# TMC6200_BOB.net
KiCad netlist of a schematic drawn in Altium Designer
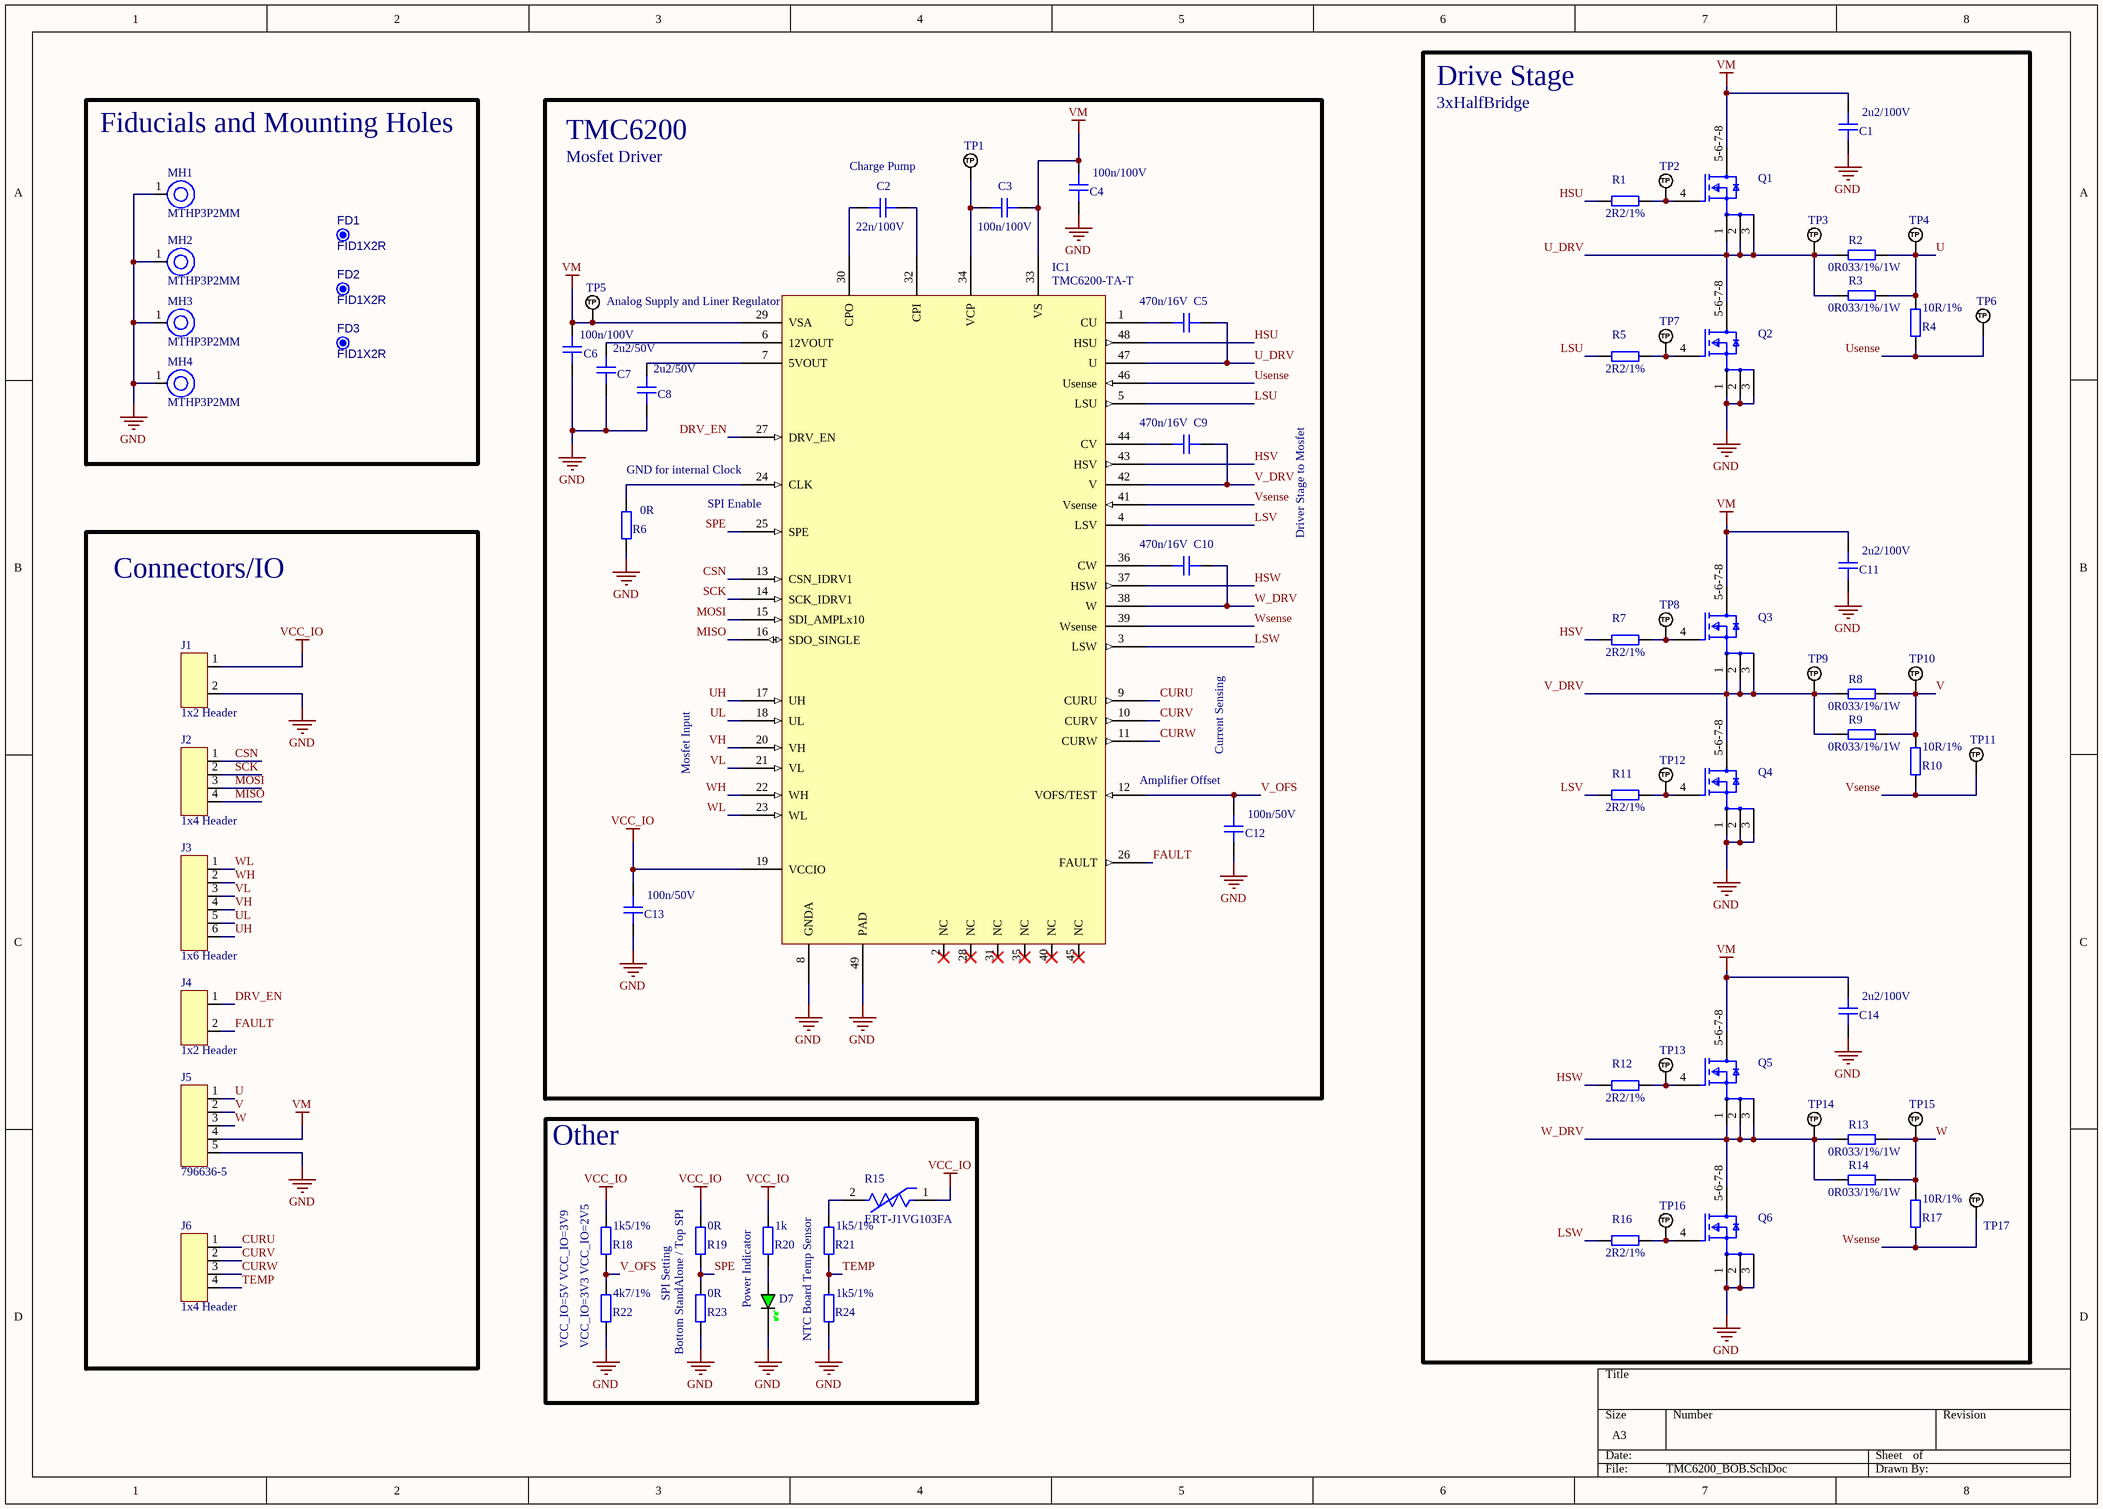
[diagram p0: TMC6200_BOB.SchDoc]

(export (version "E")
  (design (tool "Eeschema 10.0.6"))
  (components
    (comp (ref "C1")
      (value "2u2/100V")
      (footprint "CAP_1206")
      (description "Capacitor SMD 1206")
      (fields (field (name "SOURCE") "Schematic-Lib-PhilsLab.SchLib"))
      (libsource (lib "Leonhard Waibl") (part "CAP_EL_NP_5MM"))
    )
    (comp (ref "C2")
      (value "22n/100V")
      (footprint "CAP_0603")
      (description "Capacitor SMD 0603")
      (fields (field (name "SOURCE") "Schematic-Lib-PhilsLab.SchLib"))
      (libsource (lib "Leonhard Waibl") (part "CAP_EL_NP_5MM"))
    )
    (comp (ref "C3")
      (value "100n/100V")
      (footprint "CAP_0805")
      (description "Capacitor SMD 0805")
      (fields (field (name "SOURCE") "Schematic-Lib-PhilsLab.SchLib"))
      (libsource (lib "Leonhard Waibl") (part "CAP_EL_NP_5MM"))
    )
    (comp (ref "C4")
      (value "100n/100V")
      (footprint "CAP_0805")
      (description "Capacitor SMD 0805")
      (fields (field (name "SOURCE") "Schematic-Lib-PhilsLab.SchLib"))
      (libsource (lib "Leonhard Waibl") (part "CAP_EL_NP_5MM"))
    )
    (comp (ref "C5")
      (value "470n/16V")
      (footprint "CAP_0603")
      (description "Capacitor SMD 0603")
      (fields (field (name "SOURCE") "Schematic-Lib-PhilsLab.SchLib"))
      (libsource (lib "Leonhard Waibl") (part "CAP_EL_NP_5MM"))
    )
    (comp (ref "C6")
      (value "100n/100V")
      (footprint "CAP_0805")
      (description "Capacitor SMD 0805")
      (fields (field (name "SOURCE") "Schematic-Lib-PhilsLab.SchLib"))
      (libsource (lib "Leonhard Waibl") (part "CAP_EL_NP_5MM"))
    )
    (comp (ref "C7")
      (value "2u2/50V")
      (footprint "CAP_0805")
      (description "Capacitor SMD 0805")
      (fields (field (name "SOURCE") "Schematic-Lib-PhilsLab.SchLib"))
      (libsource (lib "Leonhard Waibl") (part "CAP_EL_NP_5MM"))
    )
    (comp (ref "C8")
      (value "2u2/50V")
      (footprint "CAP_0805")
      (description "Capacitor SMD 0805")
      (fields (field (name "SOURCE") "Schematic-Lib-PhilsLab.SchLib"))
      (libsource (lib "Leonhard Waibl") (part "CAP_EL_NP_5MM"))
    )
    (comp (ref "C9")
      (value "470n/16V")
      (footprint "CAP_0603")
      (description "Capacitor SMD 0603")
      (fields (field (name "SOURCE") "Schematic-Lib-PhilsLab.SchLib"))
      (libsource (lib "Leonhard Waibl") (part "CAP_EL_NP_5MM"))
    )
    (comp (ref "C10")
      (value "470n/16V")
      (footprint "CAP_0603")
      (description "Capacitor SMD 0603")
      (fields (field (name "SOURCE") "Schematic-Lib-PhilsLab.SchLib"))
      (libsource (lib "Leonhard Waibl") (part "CAP_EL_NP_5MM"))
    )
    (comp (ref "C11")
      (value "2u2/100V")
      (footprint "CAP_1206")
      (description "Capacitor SMD 1206")
      (fields (field (name "SOURCE") "Schematic-Lib-PhilsLab.SchLib"))
      (libsource (lib "Leonhard Waibl") (part "CAP_EL_NP_5MM"))
    )
    (comp (ref "C12")
      (value "100n/50V")
      (footprint "CAP_0603")
      (description "Capacitor SMD 0603")
      (fields (field (name "SOURCE") "Schematic-Lib-PhilsLab.SchLib"))
      (libsource (lib "Leonhard Waibl") (part "CAP_EL_NP_5MM"))
    )
    (comp (ref "C13")
      (value "100n/50V")
      (footprint "CAP_0603")
      (description "Capacitor SMD 0603")
      (fields (field (name "SOURCE") "Schematic-Lib-PhilsLab.SchLib"))
      (libsource (lib "Leonhard Waibl") (part "CAP_EL_NP_5MM"))
    )
    (comp (ref "C14")
      (value "2u2/100V")
      (footprint "CAP_1206")
      (description "Capacitor SMD 1206")
      (fields (field (name "SOURCE") "Schematic-Lib-PhilsLab.SchLib"))
      (libsource (lib "Leonhard Waibl") (part "CAP_EL_NP_5MM"))
    )
    (comp (ref "D7")
      (value "LED_0805_GREEN")
      (footprint "LED_0805_GREEN")
      (description "LED 0805 GREEN SMD")
      (fields (field (name "SOURCE") "Schematic-Lib-PhilsLab.SchLib"))
      (libsource (lib "Leonhard Waibl") (part "LED_0805_GREEN"))
    )
    (comp (ref "FD1")
      (value "FID1X2R")
      (footprint "FID1X2R")
      (description "Fiducial - Round 1x2mm")
      (libsource (lib "Leonhard Waibl") (part "CMP-00134-2"))
    )
    (comp (ref "FD2")
      (value "FID1X2R")
      (footprint "FID1X2R")
      (description "Fiducial - Round 1x2mm")
      (libsource (lib "Leonhard Waibl") (part "CMP-00134-2"))
    )
    (comp (ref "FD3")
      (value "FID1X2R")
      (footprint "FID1X2R")
      (description "Fiducial - Round 1x2mm")
      (libsource (lib "Leonhard Waibl") (part "CMP-00134-2"))
    )
    (comp (ref "IC1")
      (value "TMC6200-TA-T")
      (footprint "TSQFP50P900X900X120_HS-49N")
      (libsource (lib "Leonhard Waibl") (part "TMC6200-TA-T-Symbol-1"))
    )
    (comp (ref "J1")
      (value "1x2 Header")
      (footprint "1x2 Header-Footprint-1")
      (libsource (lib "Leonhard Waibl") (part "1x2 Header-Symbol-1"))
    )
    (comp (ref "J2")
      (value "1x4 Header")
      (footprint "1x4 Header-Footprint-1")
      (libsource (lib "Leonhard Waibl") (part "1x4 Header-Symbol-1"))
    )
    (comp (ref "J3")
      (value "1x6 Header")
      (footprint "1x6 Header-Footprint-1")
      (libsource (lib "Leonhard Waibl") (part "1x6 Header-Symbol-1"))
    )
    (comp (ref "J4")
      (value "1x2 Header")
      (footprint "1x2 Header-Footprint-1")
      (libsource (lib "Leonhard Waibl") (part "1x2 Header-Symbol-1"))
    )
    (comp (ref "J5")
      (value "796636-5")
      (footprint "796636-5-Footprint-1")
      (libsource (lib "Leonhard Waibl") (part "796636-Symbol"))
    )
    (comp (ref "J6")
      (value "1x4 Header")
      (footprint "1x4 Header-Footprint-1")
      (libsource (lib "Leonhard Waibl") (part "1x4 Header-Symbol-1"))
    )
    (comp (ref "MH1")
      (value "MTHP3P2MM")
      (footprint "MTHP3P2MM-Footprint-1")
      (description "Mounting Hole Plated 3.2 mm drill")
      (libsource (lib "Leonhard Waibl") (part "MTHP3P2MM"))
    )
    (comp (ref "MH2")
      (value "MTHP3P2MM")
      (footprint "MTHP3P2MM-Footprint-1")
      (description "Mounting Hole Plated 3.2 mm drill")
      (libsource (lib "Leonhard Waibl") (part "MTHP3P2MM"))
    )
    (comp (ref "MH3")
      (value "MTHP3P2MM")
      (footprint "MTHP3P2MM-Footprint-1")
      (description "Mounting Hole Plated 3.2 mm drill")
      (libsource (lib "Leonhard Waibl") (part "MTHP3P2MM"))
    )
    (comp (ref "MH4")
      (value "MTHP3P2MM")
      (footprint "MTHP3P2MM-Footprint-1")
      (description "Mounting Hole Plated 3.2 mm drill")
      (libsource (lib "Leonhard Waibl") (part "MTHP3P2MM"))
    )
    (comp (ref "Q1")
      (value "SIDR626LDP-T1-RE3")
      (footprint "FP-T21-0014-SINGLE-MFG")
      (description "Mosfet, N-Ch, 60V, 204A, Powerpak So Rohs Compliant: Yes")
      (libsource (lib "Leonhard Waibl") (part "bca9987edd56f2da107db22e16ec776"))
    )
    (comp (ref "Q2")
      (value "SIDR626LDP-T1-RE3")
      (footprint "FP-T21-0014-SINGLE-MFG")
      (description "Mosfet, N-Ch, 60V, 204A, Powerpak So Rohs Compliant: Yes")
      (libsource (lib "Leonhard Waibl") (part "bca9987edd56f2da107db22e16ec776"))
    )
    (comp (ref "Q3")
      (value "SIDR626LDP-T1-RE3")
      (footprint "FP-T21-0014-SINGLE-MFG")
      (description "Mosfet, N-Ch, 60V, 204A, Powerpak So Rohs Compliant: Yes")
      (libsource (lib "Leonhard Waibl") (part "bca9987edd56f2da107db22e16ec776"))
    )
    (comp (ref "Q4")
      (value "SIDR626LDP-T1-RE3")
      (footprint "FP-T21-0014-SINGLE-MFG")
      (description "Mosfet, N-Ch, 60V, 204A, Powerpak So Rohs Compliant: Yes")
      (libsource (lib "Leonhard Waibl") (part "bca9987edd56f2da107db22e16ec776"))
    )
    (comp (ref "Q5")
      (value "SIDR626LDP-T1-RE3")
      (footprint "FP-T21-0014-SINGLE-MFG")
      (description "Mosfet, N-Ch, 60V, 204A, Powerpak So Rohs Compliant: Yes")
      (libsource (lib "Leonhard Waibl") (part "bca9987edd56f2da107db22e16ec776"))
    )
    (comp (ref "Q6")
      (value "SIDR626LDP-T1-RE3")
      (footprint "FP-T21-0014-SINGLE-MFG")
      (description "Mosfet, N-Ch, 60V, 204A, Powerpak So Rohs Compliant: Yes")
      (libsource (lib "Leonhard Waibl") (part "bca9987edd56f2da107db22e16ec776"))
    )
    (comp (ref "R1")
      (value "2R2/1%")
      (footprint "RES_0603")
      (description "Resistor SMD 0603")
      (fields (field (name "SOURCE") "Schematic-Lib-PhilsLab.SchLib"))
      (libsource (lib "Leonhard Waibl") (part "RES_5931"))
    )
    (comp (ref "R2")
      (value "0R033/1%/1W")
      (footprint "RES_1206")
      (description "Resistor SMD 1206")
      (fields (field (name "SOURCE") "Schematic-Lib-PhilsLab.SchLib"))
      (libsource (lib "Leonhard Waibl") (part "RES_5931"))
    )
    (comp (ref "R3")
      (value "0R033/1%/1W")
      (footprint "RES_1206")
      (description "Resistor SMD 1206")
      (fields (field (name "SOURCE") "Schematic-Lib-PhilsLab.SchLib"))
      (libsource (lib "Leonhard Waibl") (part "RES_5931"))
    )
    (comp (ref "R4")
      (value "10R/1%")
      (footprint "RES_0603")
      (description "Resistor SMD 0603")
      (fields (field (name "SOURCE") "Schematic-Lib-PhilsLab.SchLib"))
      (libsource (lib "Leonhard Waibl") (part "RES_5931"))
    )
    (comp (ref "R5")
      (value "2R2/1%")
      (footprint "RES_0603")
      (description "Resistor SMD 0603")
      (fields (field (name "SOURCE") "Schematic-Lib-PhilsLab.SchLib"))
      (libsource (lib "Leonhard Waibl") (part "RES_5931"))
    )
    (comp (ref "R6")
      (value "0R")
      (footprint "RES_0603")
      (description "Resistor SMD 0603")
      (fields (field (name "SOURCE") "Schematic-Lib-PhilsLab.SchLib"))
      (libsource (lib "Leonhard Waibl") (part "RES_5931"))
    )
    (comp (ref "R7")
      (value "2R2/1%")
      (footprint "RES_0603")
      (description "Resistor SMD 0603")
      (fields (field (name "SOURCE") "Schematic-Lib-PhilsLab.SchLib"))
      (libsource (lib "Leonhard Waibl") (part "RES_5931"))
    )
    (comp (ref "R8")
      (value "0R033/1%/1W")
      (footprint "RES_1206")
      (description "Resistor SMD 1206")
      (fields (field (name "SOURCE") "Schematic-Lib-PhilsLab.SchLib"))
      (libsource (lib "Leonhard Waibl") (part "RES_5931"))
    )
    (comp (ref "R9")
      (value "0R033/1%/1W")
      (footprint "RES_1206")
      (description "Resistor SMD 1206")
      (fields (field (name "SOURCE") "Schematic-Lib-PhilsLab.SchLib"))
      (libsource (lib "Leonhard Waibl") (part "RES_5931"))
    )
    (comp (ref "R10")
      (value "10R/1%")
      (footprint "RES_0603")
      (description "Resistor SMD 0603")
      (fields (field (name "SOURCE") "Schematic-Lib-PhilsLab.SchLib"))
      (libsource (lib "Leonhard Waibl") (part "RES_5931"))
    )
    (comp (ref "R11")
      (value "2R2/1%")
      (footprint "RES_0603")
      (description "Resistor SMD 0603")
      (fields (field (name "SOURCE") "Schematic-Lib-PhilsLab.SchLib"))
      (libsource (lib "Leonhard Waibl") (part "RES_5931"))
    )
    (comp (ref "R12")
      (value "2R2/1%")
      (footprint "RES_0603")
      (description "Resistor SMD 0603")
      (fields (field (name "SOURCE") "Schematic-Lib-PhilsLab.SchLib"))
      (libsource (lib "Leonhard Waibl") (part "RES_5931"))
    )
    (comp (ref "R13")
      (value "0R033/1%/1W")
      (footprint "RES_1206")
      (description "Resistor SMD 1206")
      (fields (field (name "SOURCE") "Schematic-Lib-PhilsLab.SchLib"))
      (libsource (lib "Leonhard Waibl") (part "RES_5931"))
    )
    (comp (ref "R14")
      (value "0R033/1%/1W")
      (footprint "RES_1206")
      (description "Resistor SMD 1206")
      (fields (field (name "SOURCE") "Schematic-Lib-PhilsLab.SchLib"))
      (libsource (lib "Leonhard Waibl") (part "RES_5931"))
    )
    (comp (ref "R15")
      (value "ERT-J1VG103FA")
      (footprint "FP-ERTJ1-MFG")
      (description "THERMISTOR NTC 10KOHM 3380K 0603")
      (fields (field (name "TOLERANCE") "1%"))
      (libsource (lib "Altium Content Vault") (part "3b148a6ebabc5fb4d708a66c052d352"))
    )
    (comp (ref "R16")
      (value "2R2/1%")
      (footprint "RES_0603")
      (description "Resistor SMD 0603")
      (fields (field (name "SOURCE") "Schematic-Lib-PhilsLab.SchLib"))
      (libsource (lib "Leonhard Waibl") (part "RES_5931"))
    )
    (comp (ref "R17")
      (value "10R/1%")
      (footprint "RES_0603")
      (description "Resistor SMD 0603")
      (fields (field (name "SOURCE") "Schematic-Lib-PhilsLab.SchLib"))
      (libsource (lib "Leonhard Waibl") (part "RES_5931"))
    )
    (comp (ref "R18")
      (value "1k5/1%")
      (footprint "RES_0603")
      (description "Resistor SMD 0603")
      (fields (field (name "SOURCE") "Schematic-Lib-PhilsLab.SchLib"))
      (libsource (lib "Leonhard Waibl") (part "RES_5931"))
    )
    (comp (ref "R19")
      (value "0R")
      (footprint "RES_0603")
      (description "Resistor SMD 0603")
      (fields (field (name "SOURCE") "Schematic-Lib-PhilsLab.SchLib"))
      (libsource (lib "Leonhard Waibl") (part "RES_5931"))
    )
    (comp (ref "R20")
      (value "1k")
      (footprint "RES_0603")
      (description "Resistor SMD 0603")
      (fields (field (name "SOURCE") "Schematic-Lib-PhilsLab.SchLib"))
      (libsource (lib "Leonhard Waibl") (part "RES_5931"))
    )
    (comp (ref "R21")
      (value "1k5/1%")
      (footprint "RES_0603")
      (description "Resistor SMD 0603")
      (fields (field (name "SOURCE") "Schematic-Lib-PhilsLab.SchLib"))
      (libsource (lib "Leonhard Waibl") (part "RES_5931"))
    )
    (comp (ref "R22")
      (value "4k7/1%")
      (footprint "RES_0603")
      (description "Resistor SMD 0603")
      (fields (field (name "SOURCE") "Schematic-Lib-PhilsLab.SchLib"))
      (libsource (lib "Leonhard Waibl") (part "RES_5931"))
    )
    (comp (ref "R23")
      (value "0R")
      (footprint "RES_0603")
      (description "Resistor SMD 0603")
      (fields (field (name "SOURCE") "Schematic-Lib-PhilsLab.SchLib"))
      (libsource (lib "Leonhard Waibl") (part "RES_5931"))
    )
    (comp (ref "R24")
      (value "1k5/1%")
      (footprint "RES_0603")
      (description "Resistor SMD 0603")
      (fields (field (name "SOURCE") "Schematic-Lib-PhilsLab.SchLib"))
      (libsource (lib "Leonhard Waibl") (part "RES_5931"))
    )
    (comp (ref "TP1")
      (value "TEST_POINT_RND_1MM")
      (footprint "PAD_RND_1MM")
      (description "Test Point Round 1mm (NO BOM)")
      (fields (field (name "SOURCE") "Schematic-Lib-PhilsLab.SchLib"))
      (libsource (lib "Leonhard Waibl") (part "TEST_POINT_RND_1MM"))
    )
    (comp (ref "TP2")
      (value "TEST_POINT_RND_1MM")
      (footprint "PAD_RND_1MM")
      (description "Test Point Round 1mm (NO BOM)")
      (fields (field (name "SOURCE") "Schematic-Lib-PhilsLab.SchLib"))
      (libsource (lib "Leonhard Waibl") (part "TEST_POINT_RND_1MM"))
    )
    (comp (ref "TP3")
      (value "TEST_POINT_RND_1MM")
      (footprint "PAD_RND_1MM")
      (description "Test Point Round 1mm (NO BOM)")
      (fields (field (name "SOURCE") "Schematic-Lib-PhilsLab.SchLib"))
      (libsource (lib "Leonhard Waibl") (part "TEST_POINT_RND_1MM"))
    )
    (comp (ref "TP4")
      (value "TEST_POINT_RND_1MM")
      (footprint "PAD_RND_1MM")
      (description "Test Point Round 1mm (NO BOM)")
      (fields (field (name "SOURCE") "Schematic-Lib-PhilsLab.SchLib"))
      (libsource (lib "Leonhard Waibl") (part "TEST_POINT_RND_1MM"))
    )
    (comp (ref "TP5")
      (value "TEST_POINT_RND_1MM")
      (footprint "PAD_RND_1MM")
      (description "Test Point Round 1mm (NO BOM)")
      (fields (field (name "SOURCE") "Schematic-Lib-PhilsLab.SchLib"))
      (libsource (lib "Leonhard Waibl") (part "TEST_POINT_RND_1MM"))
    )
    (comp (ref "TP6")
      (value "TEST_POINT_RND_1MM")
      (footprint "PAD_RND_1MM")
      (description "Test Point Round 1mm (NO BOM)")
      (fields (field (name "SOURCE") "Schematic-Lib-PhilsLab.SchLib"))
      (libsource (lib "Leonhard Waibl") (part "TEST_POINT_RND_1MM"))
    )
    (comp (ref "TP7")
      (value "TEST_POINT_RND_1MM")
      (footprint "PAD_RND_1MM")
      (description "Test Point Round 1mm (NO BOM)")
      (fields (field (name "SOURCE") "Schematic-Lib-PhilsLab.SchLib"))
      (libsource (lib "Leonhard Waibl") (part "TEST_POINT_RND_1MM"))
    )
    (comp (ref "TP8")
      (value "TEST_POINT_RND_1MM")
      (footprint "PAD_RND_1MM")
      (description "Test Point Round 1mm (NO BOM)")
      (fields (field (name "SOURCE") "Schematic-Lib-PhilsLab.SchLib"))
      (libsource (lib "Leonhard Waibl") (part "TEST_POINT_RND_1MM"))
    )
    (comp (ref "TP9")
      (value "TEST_POINT_RND_1MM")
      (footprint "PAD_RND_1MM")
      (description "Test Point Round 1mm (NO BOM)")
      (fields (field (name "SOURCE") "Schematic-Lib-PhilsLab.SchLib"))
      (libsource (lib "Leonhard Waibl") (part "TEST_POINT_RND_1MM"))
    )
    (comp (ref "TP10")
      (value "TEST_POINT_RND_1MM")
      (footprint "PAD_RND_1MM")
      (description "Test Point Round 1mm (NO BOM)")
      (fields (field (name "SOURCE") "Schematic-Lib-PhilsLab.SchLib"))
      (libsource (lib "Leonhard Waibl") (part "TEST_POINT_RND_1MM"))
    )
    (comp (ref "TP11")
      (value "TEST_POINT_RND_1MM")
      (footprint "PAD_RND_1MM")
      (description "Test Point Round 1mm (NO BOM)")
      (fields (field (name "SOURCE") "Schematic-Lib-PhilsLab.SchLib"))
      (libsource (lib "Leonhard Waibl") (part "TEST_POINT_RND_1MM"))
    )
    (comp (ref "TP12")
      (value "TEST_POINT_RND_1MM")
      (footprint "PAD_RND_1MM")
      (description "Test Point Round 1mm (NO BOM)")
      (fields (field (name "SOURCE") "Schematic-Lib-PhilsLab.SchLib"))
      (libsource (lib "Leonhard Waibl") (part "TEST_POINT_RND_1MM"))
    )
    (comp (ref "TP13")
      (value "TEST_POINT_RND_1MM")
      (footprint "PAD_RND_1MM")
      (description "Test Point Round 1mm (NO BOM)")
      (fields (field (name "SOURCE") "Schematic-Lib-PhilsLab.SchLib"))
      (libsource (lib "Leonhard Waibl") (part "TEST_POINT_RND_1MM"))
    )
    (comp (ref "TP14")
      (value "TEST_POINT_RND_1MM")
      (footprint "PAD_RND_1MM")
      (description "Test Point Round 1mm (NO BOM)")
      (fields (field (name "SOURCE") "Schematic-Lib-PhilsLab.SchLib"))
      (libsource (lib "Leonhard Waibl") (part "TEST_POINT_RND_1MM"))
    )
    (comp (ref "TP15")
      (value "TEST_POINT_RND_1MM")
      (footprint "PAD_RND_1MM")
      (description "Test Point Round 1mm (NO BOM)")
      (fields (field (name "SOURCE") "Schematic-Lib-PhilsLab.SchLib"))
      (libsource (lib "Leonhard Waibl") (part "TEST_POINT_RND_1MM"))
    )
    (comp (ref "TP16")
      (value "TEST_POINT_RND_1MM")
      (footprint "PAD_RND_1MM")
      (description "Test Point Round 1mm (NO BOM)")
      (fields (field (name "SOURCE") "Schematic-Lib-PhilsLab.SchLib"))
      (libsource (lib "Leonhard Waibl") (part "TEST_POINT_RND_1MM"))
    )
    (comp (ref "TP17")
      (value "TEST_POINT_RND_1MM")
      (footprint "PAD_RND_1MM")
      (description "Test Point Round 1mm (NO BOM)")
      (fields (field (name "SOURCE") "Schematic-Lib-PhilsLab.SchLib"))
      (libsource (lib "Leonhard Waibl") (part "TEST_POINT_RND_1MM"))
    )
  )
  (nets
    (net (code "1") (name "/CSN") (class "Default")
      (node (ref "IC1") (pin "13") (pinfunction "CSN_IDRV1_13") (pintype "input"))
      (node (ref "J2") (pin "1") (pinfunction "1_1") (pintype "passive"))
    )
    (net (code "2") (name "/CURU") (class "Default")
      (node (ref "IC1") (pin "9") (pinfunction "CURU_9") (pintype "output"))
      (node (ref "J6") (pin "1") (pinfunction "1_1") (pintype "passive"))
    )
    (net (code "3") (name "/CURV") (class "Default")
      (node (ref "IC1") (pin "10") (pinfunction "CURV_10") (pintype "output"))
      (node (ref "J6") (pin "2") (pinfunction "2_2") (pintype "passive"))
    )
    (net (code "4") (name "/CURW") (class "Default")
      (node (ref "IC1") (pin "11") (pinfunction "CURW_11") (pintype "output"))
      (node (ref "J6") (pin "3") (pinfunction "3_3") (pintype "passive"))
    )
    (net (code "5") (name "/DRV_EN") (class "Default")
      (node (ref "IC1") (pin "27") (pinfunction "DRV_EN_27") (pintype "input"))
      (node (ref "J4") (pin "1") (pinfunction "1_1") (pintype "passive"))
    )
    (net (code "6") (name "/FAULT") (class "Default")
      (node (ref "IC1") (pin "26") (pinfunction "FAULT_26") (pintype "output"))
      (node (ref "J4") (pin "2") (pinfunction "2_2") (pintype "passive"))
    )
    (net (code "7") (name "/HSU") (class "Default")
      (node (ref "IC1") (pin "48") (pinfunction "HSU_48") (pintype "output"))
      (node (ref "R1") (pin "1") (pinfunction "1_1") (pintype "passive"))
    )
    (net (code "8") (name "/HSV") (class "Default")
      (node (ref "IC1") (pin "43") (pinfunction "HSV_43") (pintype "output"))
      (node (ref "R7") (pin "1") (pinfunction "1_1") (pintype "passive"))
    )
    (net (code "9") (name "/HSW") (class "Default")
      (node (ref "IC1") (pin "37") (pinfunction "HSW_37") (pintype "output"))
      (node (ref "R12") (pin "1") (pinfunction "1_1") (pintype "passive"))
    )
    (net (code "10") (name "/LSU") (class "Default")
      (node (ref "IC1") (pin "5") (pinfunction "LSU_5") (pintype "output"))
      (node (ref "R5") (pin "1") (pinfunction "1_1") (pintype "passive"))
    )
    (net (code "11") (name "/LSV") (class "Default")
      (node (ref "IC1") (pin "4") (pinfunction "LSV_4") (pintype "passive"))
      (node (ref "R11") (pin "1") (pinfunction "1_1") (pintype "passive"))
    )
    (net (code "12") (name "/LSW") (class "Default")
      (node (ref "IC1") (pin "3") (pinfunction "LSW_3") (pintype "output"))
      (node (ref "R16") (pin "1") (pinfunction "1_1") (pintype "passive"))
    )
    (net (code "13") (name "/MISO") (class "Default")
      (node (ref "IC1") (pin "16") (pinfunction "SDO_SINGLE_16") (pintype "bidirectional"))
      (node (ref "J2") (pin "4") (pinfunction "4_4") (pintype "passive"))
    )
    (net (code "14") (name "/MOSI") (class "Default")
      (node (ref "IC1") (pin "15") (pinfunction "SDI_AMPLx10_15") (pintype "input"))
      (node (ref "J2") (pin "3") (pinfunction "3_3") (pintype "passive"))
    )
    (net (code "15") (name "/SCK") (class "Default")
      (node (ref "IC1") (pin "14") (pinfunction "SCK_IDRV1_14") (pintype "input"))
      (node (ref "J2") (pin "2") (pinfunction "2_2") (pintype "passive"))
    )
    (net (code "16") (name "/SPE") (class "Default")
      (node (ref "IC1") (pin "25") (pinfunction "SPE_25") (pintype "input"))
      (node (ref "R19") (pin "1") (pinfunction "1_1") (pintype "passive"))
      (node (ref "R23") (pin "2") (pinfunction "2_2") (pintype "passive"))
    )
    (net (code "17") (name "/TEMP") (class "Default")
      (node (ref "J6") (pin "4") (pinfunction "4_4") (pintype "passive"))
      (node (ref "R21") (pin "1") (pinfunction "1_1") (pintype "passive"))
      (node (ref "R24") (pin "2") (pinfunction "2_2") (pintype "passive"))
    )
    (net (code "18") (name "/U") (class "Default")
      (node (ref "J5") (pin "1") (pinfunction "1_1") (pintype "passive"))
      (node (ref "R2") (pin "2") (pinfunction "2_2") (pintype "passive"))
      (node (ref "R3") (pin "2") (pinfunction "2_2") (pintype "passive"))
      (node (ref "R4") (pin "2") (pinfunction "2_2") (pintype "passive"))
      (node (ref "TP4") (pin "1") (pinfunction "TP_1") (pintype "passive"))
    )
    (net (code "19") (name "/UH") (class "Default")
      (node (ref "IC1") (pin "17") (pinfunction "UH_17") (pintype "input"))
      (node (ref "J3") (pin "6") (pinfunction "6_6") (pintype "passive"))
    )
    (net (code "20") (name "/UL") (class "Default")
      (node (ref "IC1") (pin "18") (pinfunction "UL_18") (pintype "input"))
      (node (ref "J3") (pin "5") (pinfunction "5_5") (pintype "passive"))
    )
    (net (code "21") (name "/U_DRV") (class "Default")
      (node (ref "C5") (pin "2") (pinfunction "2_2") (pintype "passive"))
      (node (ref "IC1") (pin "47") (pinfunction "U_47") (pintype "passive"))
      (node (ref "Q1") (pin "1") (pinfunction "S_1") (pintype "passive"))
      (node (ref "Q1") (pin "2") (pinfunction "S_2") (pintype "passive"))
      (node (ref "Q1") (pin "3") (pinfunction "S_3") (pintype "passive"))
      (node (ref "Q2") (pin "5-6-7-8") (pinfunction "D_5-6-7-8") (pintype "passive"))
      (node (ref "R2") (pin "1") (pinfunction "1_1") (pintype "passive"))
      (node (ref "R3") (pin "1") (pinfunction "1_1") (pintype "passive"))
      (node (ref "TP3") (pin "1") (pinfunction "TP_1") (pintype "passive"))
    )
    (net (code "22") (name "/Usense") (class "Default")
      (node (ref "IC1") (pin "46") (pinfunction "Usense_46") (pintype "input"))
      (node (ref "R4") (pin "1") (pinfunction "1_1") (pintype "passive"))
      (node (ref "TP6") (pin "1") (pinfunction "TP_1") (pintype "passive"))
    )
    (net (code "23") (name "/V") (class "Default")
      (node (ref "J5") (pin "2") (pinfunction "2_2") (pintype "passive"))
      (node (ref "R10") (pin "2") (pinfunction "2_2") (pintype "passive"))
      (node (ref "R8") (pin "2") (pinfunction "2_2") (pintype "passive"))
      (node (ref "R9") (pin "2") (pinfunction "2_2") (pintype "passive"))
      (node (ref "TP10") (pin "1") (pinfunction "TP_1") (pintype "passive"))
    )
    (net (code "24") (name "/VH") (class "Default")
      (node (ref "IC1") (pin "20") (pinfunction "VH_20") (pintype "input"))
      (node (ref "J3") (pin "4") (pinfunction "4_4") (pintype "passive"))
    )
    (net (code "25") (name "/VL") (class "Default")
      (node (ref "IC1") (pin "21") (pinfunction "VL_21") (pintype "input"))
      (node (ref "J3") (pin "3") (pinfunction "3_3") (pintype "passive"))
    )
    (net (code "26") (name "/V_DRV") (class "Default")
      (node (ref "C9") (pin "2") (pinfunction "2_2") (pintype "passive"))
      (node (ref "IC1") (pin "42") (pinfunction "V_42") (pintype "passive"))
      (node (ref "Q3") (pin "1") (pinfunction "S_1") (pintype "passive"))
      (node (ref "Q3") (pin "2") (pinfunction "S_2") (pintype "passive"))
      (node (ref "Q3") (pin "3") (pinfunction "S_3") (pintype "passive"))
      (node (ref "Q4") (pin "5-6-7-8") (pinfunction "D_5-6-7-8") (pintype "passive"))
      (node (ref "R8") (pin "1") (pinfunction "1_1") (pintype "passive"))
      (node (ref "R9") (pin "1") (pinfunction "1_1") (pintype "passive"))
      (node (ref "TP9") (pin "1") (pinfunction "TP_1") (pintype "passive"))
    )
    (net (code "27") (name "/V_OFS") (class "Default")
      (node (ref "C12") (pin "2") (pinfunction "2_2") (pintype "passive"))
      (node (ref "IC1") (pin "12") (pinfunction "VOFS/TEST_12") (pintype "input"))
      (node (ref "R18") (pin "1") (pinfunction "1_1") (pintype "passive"))
      (node (ref "R22") (pin "2") (pinfunction "2_2") (pintype "passive"))
    )
    (net (code "28") (name "/Vsense") (class "Default")
      (node (ref "IC1") (pin "41") (pinfunction "Vsense_41") (pintype "input"))
      (node (ref "R10") (pin "1") (pinfunction "1_1") (pintype "passive"))
      (node (ref "TP11") (pin "1") (pinfunction "TP_1") (pintype "passive"))
    )
    (net (code "29") (name "/W") (class "Default")
      (node (ref "J5") (pin "3") (pinfunction "3_3") (pintype "passive"))
      (node (ref "R13") (pin "2") (pinfunction "2_2") (pintype "passive"))
      (node (ref "R14") (pin "2") (pinfunction "2_2") (pintype "passive"))
      (node (ref "R17") (pin "2") (pinfunction "2_2") (pintype "passive"))
      (node (ref "TP15") (pin "1") (pinfunction "TP_1") (pintype "passive"))
    )
    (net (code "30") (name "/WH") (class "Default")
      (node (ref "IC1") (pin "22") (pinfunction "WH_22") (pintype "input"))
      (node (ref "J3") (pin "2") (pinfunction "2_2") (pintype "passive"))
    )
    (net (code "31") (name "/WL") (class "Default")
      (node (ref "IC1") (pin "23") (pinfunction "WL_23") (pintype "input"))
      (node (ref "J3") (pin "1") (pinfunction "1_1") (pintype "passive"))
    )
    (net (code "32") (name "/W_DRV") (class "Default")
      (node (ref "C10") (pin "2") (pinfunction "2_2") (pintype "passive"))
      (node (ref "IC1") (pin "38") (pinfunction "W_38") (pintype "passive"))
      (node (ref "Q5") (pin "1") (pinfunction "S_1") (pintype "passive"))
      (node (ref "Q5") (pin "2") (pinfunction "S_2") (pintype "passive"))
      (node (ref "Q5") (pin "3") (pinfunction "S_3") (pintype "passive"))
      (node (ref "Q6") (pin "5-6-7-8") (pinfunction "D_5-6-7-8") (pintype "passive"))
      (node (ref "R13") (pin "1") (pinfunction "1_1") (pintype "passive"))
      (node (ref "R14") (pin "1") (pinfunction "1_1") (pintype "passive"))
      (node (ref "TP14") (pin "1") (pinfunction "TP_1") (pintype "passive"))
    )
    (net (code "33") (name "/Wsense") (class "Default")
      (node (ref "IC1") (pin "39") (pinfunction "Wsense_39") (pintype "passive"))
      (node (ref "R17") (pin "1") (pinfunction "1_1") (pintype "passive"))
      (node (ref "TP17") (pin "1") (pinfunction "TP_1") (pintype "passive"))
    )
    (net (code "34") (name "GND") (class "Default")
      (node (ref "C1") (pin "1") (pinfunction "1_1") (pintype "passive"))
      (node (ref "C11") (pin "1") (pinfunction "1_1") (pintype "passive"))
      (node (ref "C12") (pin "1") (pinfunction "1_1") (pintype "passive"))
      (node (ref "C13") (pin "2") (pinfunction "2_2") (pintype "passive"))
      (node (ref "C14") (pin "1") (pinfunction "1_1") (pintype "passive"))
      (node (ref "C4") (pin "1") (pinfunction "1_1") (pintype "passive"))
      (node (ref "C6") (pin "1") (pinfunction "1_1") (pintype "passive"))
      (node (ref "C7") (pin "1") (pinfunction "1_1") (pintype "passive"))
      (node (ref "C8") (pin "1") (pinfunction "1_1") (pintype "passive"))
      (node (ref "D7") (pin "K") (pinfunction "K_K") (pintype "passive"))
      (node (ref "IC1") (pin "49") (pinfunction "PAD_49") (pintype "power_in"))
      (node (ref "IC1") (pin "8") (pinfunction "GNDA_8") (pintype "passive"))
      (node (ref "J1") (pin "2") (pinfunction "2_2") (pintype "passive"))
      (node (ref "J5") (pin "5") (pinfunction "5_5") (pintype "passive"))
      (node (ref "MH1") (pin "1") (pinfunction "1_1") (pintype "passive"))
      (node (ref "MH2") (pin "1") (pinfunction "1_1") (pintype "passive"))
      (node (ref "MH3") (pin "1") (pinfunction "1_1") (pintype "passive"))
      (node (ref "MH4") (pin "1") (pinfunction "1_1") (pintype "passive"))
      (node (ref "Q2") (pin "1") (pinfunction "S_1") (pintype "passive"))
      (node (ref "Q2") (pin "2") (pinfunction "S_2") (pintype "passive"))
      (node (ref "Q2") (pin "3") (pinfunction "S_3") (pintype "passive"))
      (node (ref "Q4") (pin "1") (pinfunction "S_1") (pintype "passive"))
      (node (ref "Q4") (pin "2") (pinfunction "S_2") (pintype "passive"))
      (node (ref "Q4") (pin "3") (pinfunction "S_3") (pintype "passive"))
      (node (ref "Q6") (pin "1") (pinfunction "S_1") (pintype "passive"))
      (node (ref "Q6") (pin "2") (pinfunction "S_2") (pintype "passive"))
      (node (ref "Q6") (pin "3") (pinfunction "S_3") (pintype "passive"))
      (node (ref "R22") (pin "1") (pinfunction "1_1") (pintype "passive"))
      (node (ref "R23") (pin "1") (pinfunction "1_1") (pintype "passive"))
      (node (ref "R24") (pin "1") (pinfunction "1_1") (pintype "passive"))
      (node (ref "R6") (pin "1") (pinfunction "1_1") (pintype "passive"))
    )
    (net (code "35") (name "Net-(D7-PadA)") (class "Default")
      (node (ref "D7") (pin "A") (pinfunction "A_A") (pintype "passive"))
      (node (ref "R20") (pin "1") (pinfunction "1_1") (pintype "passive"))
    )
    (net (code "36") (name "Net-(IC1-5VOUT)") (class "Default")
      (node (ref "C8") (pin "2") (pinfunction "2_2") (pintype "passive"))
      (node (ref "IC1") (pin "7") (pinfunction "5VOUT_7") (pintype "passive"))
    )
    (net (code "37") (name "Net-(IC1-12VOUT)") (class "Default")
      (node (ref "C7") (pin "2") (pinfunction "2_2") (pintype "passive"))
      (node (ref "IC1") (pin "6") (pinfunction "12VOUT_6") (pintype "passive"))
    )
    (net (code "38") (name "Net-(IC1-CLK)") (class "Default")
      (node (ref "IC1") (pin "24") (pinfunction "CLK_24") (pintype "input"))
      (node (ref "R6") (pin "2") (pinfunction "2_2") (pintype "passive"))
    )
    (net (code "39") (name "Net-(IC1-CPI)") (class "Default")
      (node (ref "C2") (pin "2") (pinfunction "2_2") (pintype "passive"))
      (node (ref "IC1") (pin "32") (pinfunction "CPI_32") (pintype "passive"))
    )
    (net (code "40") (name "Net-(IC1-CPO)") (class "Default")
      (node (ref "C2") (pin "1") (pinfunction "1_1") (pintype "passive"))
      (node (ref "IC1") (pin "30") (pinfunction "CPO_30") (pintype "passive"))
    )
    (net (code "41") (name "Net-(IC1-CU)") (class "Default")
      (node (ref "C5") (pin "1") (pinfunction "1_1") (pintype "passive"))
      (node (ref "IC1") (pin "1") (pinfunction "CU_1") (pintype "passive"))
    )
    (net (code "42") (name "Net-(IC1-CV)") (class "Default")
      (node (ref "C9") (pin "1") (pinfunction "1_1") (pintype "passive"))
      (node (ref "IC1") (pin "44") (pinfunction "CV_44") (pintype "passive"))
    )
    (net (code "43") (name "Net-(IC1-CW)") (class "Default")
      (node (ref "C10") (pin "1") (pinfunction "1_1") (pintype "passive"))
      (node (ref "IC1") (pin "36") (pinfunction "CW_36") (pintype "passive"))
    )
    (net (code "44") (name "Net-(IC1-VCP)") (class "Default")
      (node (ref "C3") (pin "1") (pinfunction "1_1") (pintype "passive"))
      (node (ref "IC1") (pin "34") (pinfunction "VCP_34") (pintype "passive"))
      (node (ref "TP1") (pin "1") (pinfunction "TP_1") (pintype "passive"))
    )
    (net (code "45") (name "Net-(Q1-G)") (class "Default")
      (node (ref "Q1") (pin "4") (pinfunction "G_4") (pintype "passive"))
      (node (ref "R1") (pin "2") (pinfunction "2_2") (pintype "passive"))
      (node (ref "TP2") (pin "1") (pinfunction "TP_1") (pintype "passive"))
    )
    (net (code "46") (name "Net-(Q2-G)") (class "Default")
      (node (ref "Q2") (pin "4") (pinfunction "G_4") (pintype "passive"))
      (node (ref "R5") (pin "2") (pinfunction "2_2") (pintype "passive"))
      (node (ref "TP7") (pin "1") (pinfunction "TP_1") (pintype "passive"))
    )
    (net (code "47") (name "Net-(Q3-G)") (class "Default")
      (node (ref "Q3") (pin "4") (pinfunction "G_4") (pintype "passive"))
      (node (ref "R7") (pin "2") (pinfunction "2_2") (pintype "passive"))
      (node (ref "TP8") (pin "1") (pinfunction "TP_1") (pintype "passive"))
    )
    (net (code "48") (name "Net-(Q4-G)") (class "Default")
      (node (ref "Q4") (pin "4") (pinfunction "G_4") (pintype "passive"))
      (node (ref "R11") (pin "2") (pinfunction "2_2") (pintype "passive"))
      (node (ref "TP12") (pin "1") (pinfunction "TP_1") (pintype "passive"))
    )
    (net (code "49") (name "Net-(Q5-G)") (class "Default")
      (node (ref "Q5") (pin "4") (pinfunction "G_4") (pintype "passive"))
      (node (ref "R12") (pin "2") (pinfunction "2_2") (pintype "passive"))
      (node (ref "TP13") (pin "1") (pinfunction "TP_1") (pintype "passive"))
    )
    (net (code "50") (name "Net-(Q6-G)") (class "Default")
      (node (ref "Q6") (pin "4") (pinfunction "G_4") (pintype "passive"))
      (node (ref "R16") (pin "2") (pinfunction "2_2") (pintype "passive"))
      (node (ref "TP16") (pin "1") (pinfunction "TP_1") (pintype "passive"))
    )
    (net (code "51") (name "Net-(R15-Pad2)") (class "Default")
      (node (ref "R15") (pin "2") (pinfunction "2_2") (pintype "passive"))
      (node (ref "R21") (pin "2") (pinfunction "2_2") (pintype "passive"))
    )
    (net (code "52") (name "VCC_IO") (class "Default")
      (node (ref "C13") (pin "1") (pinfunction "1_1") (pintype "passive"))
      (node (ref "IC1") (pin "19") (pinfunction "VCCIO_19") (pintype "power_in"))
      (node (ref "J1") (pin "1") (pinfunction "1_1") (pintype "passive"))
      (node (ref "R15") (pin "1") (pinfunction "1_1") (pintype "passive"))
      (node (ref "R18") (pin "2") (pinfunction "2_2") (pintype "passive"))
      (node (ref "R19") (pin "2") (pinfunction "2_2") (pintype "passive"))
      (node (ref "R20") (pin "2") (pinfunction "2_2") (pintype "passive"))
    )
    (net (code "53") (name "VM") (class "Default")
      (node (ref "C1") (pin "2") (pinfunction "2_2") (pintype "passive"))
      (node (ref "C11") (pin "2") (pinfunction "2_2") (pintype "passive"))
      (node (ref "C14") (pin "2") (pinfunction "2_2") (pintype "passive"))
      (node (ref "C3") (pin "2") (pinfunction "2_2") (pintype "passive"))
      (node (ref "C4") (pin "2") (pinfunction "2_2") (pintype "passive"))
      (node (ref "C6") (pin "2") (pinfunction "2_2") (pintype "passive"))
      (node (ref "IC1") (pin "29") (pinfunction "VSA_29") (pintype "passive"))
      (node (ref "IC1") (pin "33") (pinfunction "VS_33") (pintype "passive"))
      (node (ref "J5") (pin "4") (pinfunction "4_4") (pintype "passive"))
      (node (ref "Q1") (pin "5-6-7-8") (pinfunction "D_5-6-7-8") (pintype "passive"))
      (node (ref "Q3") (pin "5-6-7-8") (pinfunction "D_5-6-7-8") (pintype "passive"))
      (node (ref "Q5") (pin "5-6-7-8") (pinfunction "D_5-6-7-8") (pintype "passive"))
      (node (ref "TP5") (pin "1") (pinfunction "TP_1") (pintype "passive"))
    )
    (net (code "54") (name "unconnected-(IC1-NC-Pad2)") (class "Default")
      (node (ref "IC1") (pin "2") (pinfunction "NC_2") (pintype "passive+no_connect"))
    )
    (net (code "55") (name "unconnected-(IC1-NC-Pad28)") (class "Default")
      (node (ref "IC1") (pin "28") (pinfunction "NC_28") (pintype "passive+no_connect"))
    )
    (net (code "56") (name "unconnected-(IC1-NC-Pad31)") (class "Default")
      (node (ref "IC1") (pin "31") (pinfunction "NC_31") (pintype "passive+no_connect"))
    )
    (net (code "57") (name "unconnected-(IC1-NC-Pad35)") (class "Default")
      (node (ref "IC1") (pin "35") (pinfunction "NC_35") (pintype "passive+no_connect"))
    )
    (net (code "58") (name "unconnected-(IC1-NC-Pad40)") (class "Default")
      (node (ref "IC1") (pin "40") (pinfunction "NC_40") (pintype "passive+no_connect"))
    )
    (net (code "59") (name "unconnected-(IC1-NC-Pad45)") (class "Default")
      (node (ref "IC1") (pin "45") (pinfunction "NC_45") (pintype "passive+no_connect"))
    )
  )
)
